# supplies.net
KiCad netlist of a schematic drawn in Altium Designer
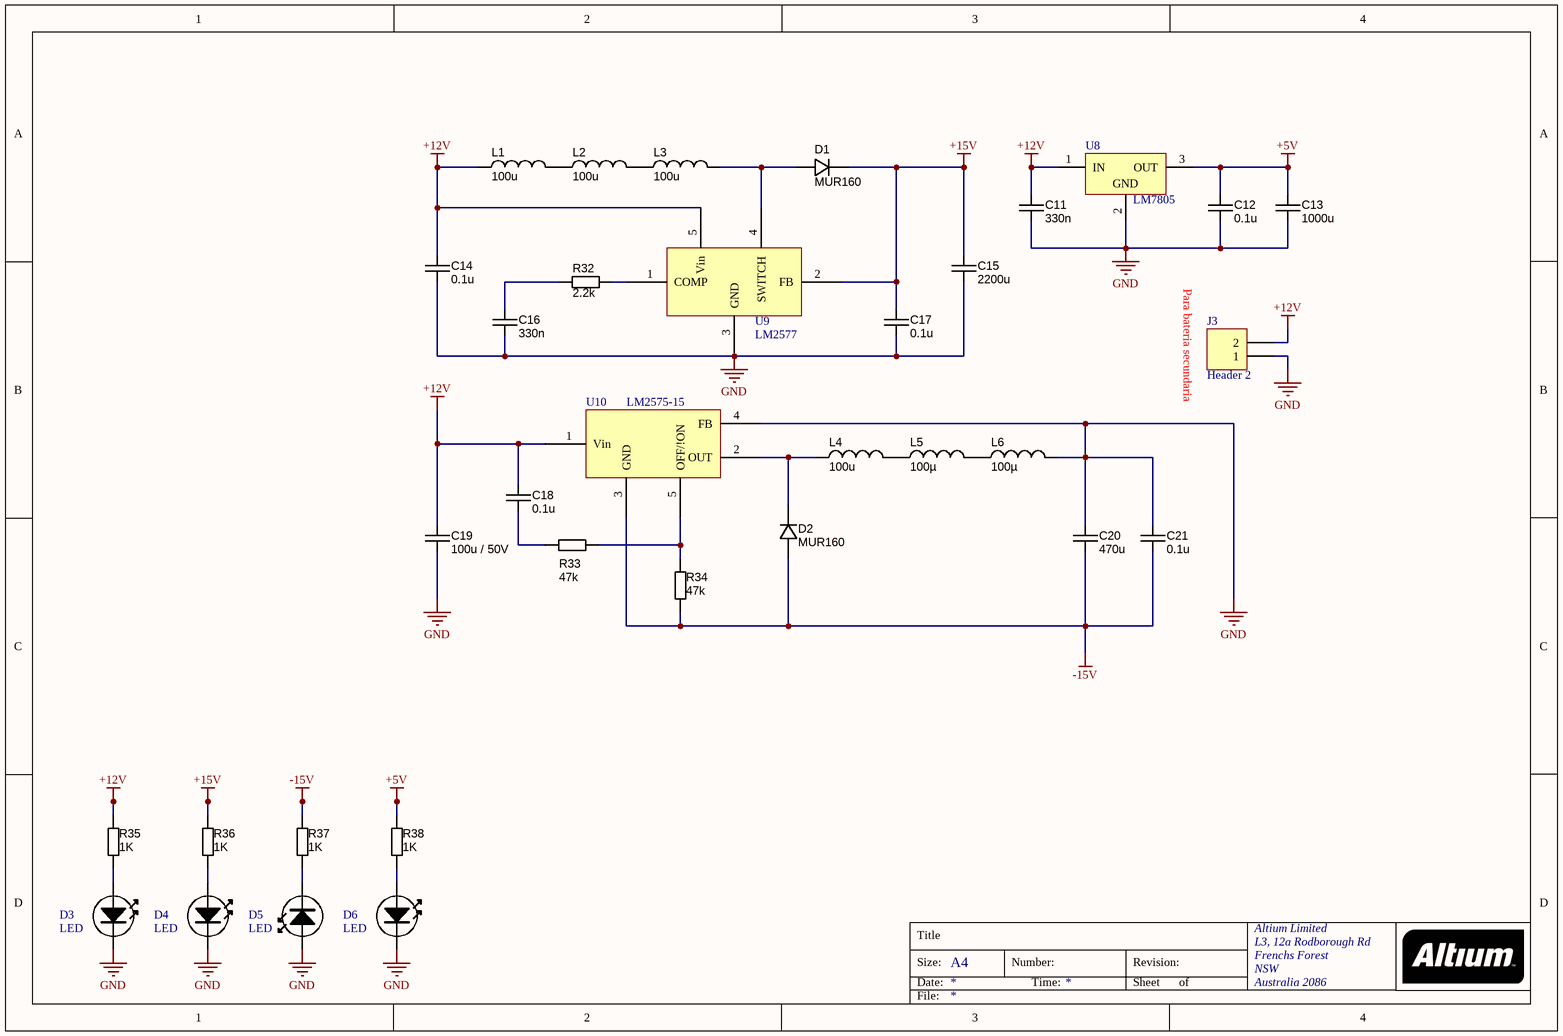
[diagram p0: supplies.SchDoc]

(export (version "E")
  (design (tool "Eeschema 10.0.6"))
  (components
    (comp (ref "C11")
      (value "330n")
      (footprint "cap33n63v")
      (description "Capacitor SMD Cer 330nF 10% 25V X7R 0805")
      (fields (field (name "TOLERANCE") "±10%") (field (name "MANUFACTURER") "Kemet"))
      (libsource (lib "PBL - Capacitors") (part "CAPC_330n_0805"))
    )
    (comp (ref "C12")
      (value "0.1u")
      (footprint "cap100n")
      (description "Capacitor SMD Cer 330nF 10% 25V X7R 0805")
      (fields (field (name "TOLERANCE") "±10%") (field (name "MANUFACTURER") "Kemet"))
      (libsource (lib "PBL - Capacitors") (part "CAPC_330n_0805"))
    )
    (comp (ref "C13")
      (value "1000u")
      (footprint "cap1000u25v")
      (description "Capacitor SMD Cer 330nF 10% 25V X7R 0805")
      (fields (field (name "TOLERANCE") "±10%") (field (name "MANUFACTURER") "Kemet"))
      (libsource (lib "PBL - Capacitors") (part "CAPC_330n_0805"))
    )
    (comp (ref "C14")
      (value "0.1u")
      (footprint "cap100n")
      (description "Capacitor SMD Cer 330nF 10% 25V X7R 0805")
      (fields (field (name "TOLERANCE") "±10%") (field (name "MANUFACTURER") "Kemet"))
      (libsource (lib "PBL - Capacitors") (part "CAPC_330n_0805"))
    )
    (comp (ref "C15")
      (value "2200u")
      (footprint "cap2200u25v")
      (description "Capacitor SMD Cer 330nF 10% 25V X7R 0805")
      (fields (field (name "TOLERANCE") "±10%") (field (name "MANUFACTURER") "Kemet"))
      (libsource (lib "PBL - Capacitors") (part "CAPC_330n_0805"))
    )
    (comp (ref "C16")
      (value "330n")
      (footprint "cap33n63v")
      (description "Capacitor SMD Cer 330nF 10% 25V X7R 0805")
      (fields (field (name "TOLERANCE") "±10%") (field (name "MANUFACTURER") "Kemet"))
      (libsource (lib "PBL - Capacitors") (part "CAPC_330n_0805"))
    )
    (comp (ref "C17")
      (value "0.1u")
      (footprint "cap100n")
      (description "Capacitor SMD Cer 330nF 10% 25V X7R 0805")
      (fields (field (name "TOLERANCE") "±10%") (field (name "MANUFACTURER") "Kemet"))
      (libsource (lib "PBL - Capacitors") (part "CAPC_330n_0805"))
    )
    (comp (ref "C18")
      (value "0.1u")
      (footprint "cap100n")
      (description "Capacitor SMD Cer 330nF 10% 25V X7R 0805")
      (fields (field (name "TOLERANCE") "±10%") (field (name "MANUFACTURER") "Kemet"))
      (libsource (lib "PBL - Capacitors") (part "CAPC_330n_0805"))
    )
    (comp (ref "C19")
      (value "100u / 50V")
      (footprint "cap100u35v")
      (description "Capacitor SMD Cer 330nF 10% 25V X7R 0805")
      (fields (field (name "TOLERANCE") "±10%") (field (name "MANUFACTURER") "Kemet"))
      (libsource (lib "PBL - Capacitors") (part "CAPC_330n_0805"))
    )
    (comp (ref "C20")
      (value "470u")
      (footprint "cap470u50v")
      (description "Capacitor SMD Cer 330nF 10% 25V X7R 0805")
      (fields (field (name "TOLERANCE") "±10%") (field (name "MANUFACTURER") "Kemet"))
      (libsource (lib "PBL - Capacitors") (part "CAPC_330n_0805"))
    )
    (comp (ref "C21")
      (value "0.1u")
      (footprint "cap100n")
      (description "Capacitor SMD Cer 330nF 10% 25V X7R 0805")
      (fields (field (name "TOLERANCE") "±10%") (field (name "MANUFACTURER") "Kemet"))
      (libsource (lib "PBL - Capacitors") (part "CAPC_330n_0805"))
    )
    (comp (ref "D1")
      (value "MUR160")
      (footprint "DO-41")
      (description "Diode 1N4007 1A 1000V THD")
      (libsource (lib "PBL - Diodes") (part "DIODE_1N4007_1000V_1.0A_DO-41"))
    )
    (comp (ref "D2")
      (value "MUR160")
      (footprint "DO-41")
      (description "Diode 1N4007 1A 1000V THD")
      (libsource (lib "PBL - Diodes") (part "DIODE_1N4007_1000V_1.0A_DO-41"))
    )
    (comp (ref "D3")
      (value "LED")
      (footprint "LED-3MM-BLUE")
      (description "LED-BLUE-3MM")
      (libsource (lib "vh_altium_library") (part "LED-BLUE-3MM"))
    )
    (comp (ref "D4")
      (value "LED")
      (footprint "LED-3MM-BLUE")
      (description "LED-BLUE-3MM")
      (libsource (lib "vh_altium_library") (part "LED-BLUE-3MM"))
    )
    (comp (ref "D5")
      (value "LED")
      (footprint "LED-3MM-BLUE")
      (description "LED-BLUE-3MM")
      (libsource (lib "vh_altium_library") (part "LED-BLUE-3MM"))
    )
    (comp (ref "D6")
      (value "LED")
      (footprint "LED-3MM-BLUE")
      (description "LED-BLUE-3MM")
      (libsource (lib "vh_altium_library") (part "LED-BLUE-3MM"))
    )
    (comp (ref "J3")
      (value "Header 2")
      (footprint "HDR1X2")
      (description "Header, 2-Pin")
      (fields (field (name "PUBLISHER") "Altium Limited"))
      (libsource (lib "Miscellaneous Connectors") (part "Header 2"))
    )
    (comp (ref "L1")
      (value "100u")
      (footprint "Inductor")
      (description "Power Inductor 180µH 10% SMD Toroid")
      (fields (field (name "TOLERANCE") "±10%") (field (name "Comment") "INDC_180u_Toroid"))
      (libsource (lib "PBL - Inductors") (part "INDC_180u_Toroid"))
    )
    (comp (ref "L2")
      (value "100u")
      (footprint "Inductor")
      (description "Power Inductor 180µH 10% SMD Toroid")
      (fields (field (name "TOLERANCE") "±10%") (field (name "Comment") "INDC_180u_Toroid"))
      (libsource (lib "PBL - Inductors") (part "INDC_180u_Toroid"))
    )
    (comp (ref "L3")
      (value "100u")
      (footprint "Inductor")
      (description "Power Inductor 180µH 10% SMD Toroid")
      (fields (field (name "TOLERANCE") "±10%") (field (name "Comment") "INDC_180u_Toroid"))
      (libsource (lib "PBL - Inductors") (part "INDC_180u_Toroid"))
    )
    (comp (ref "L4")
      (value "100u")
      (footprint "Inductor")
      (description "Power Inductor 180µH 10% SMD Toroid")
      (fields (field (name "TOLERANCE") "±10%") (field (name "Comment") "INDC_180u_Toroid"))
      (libsource (lib "PBL - Inductors") (part "INDC_180u_Toroid"))
    )
    (comp (ref "L5")
      (value "100µ")
      (footprint "Inductor")
      (description "Power Inductor 180µH 10% SMD Toroid")
      (fields (field (name "TOLERANCE") "±10%") (field (name "Comment") "INDC_180u_Toroid"))
      (libsource (lib "PBL - Inductors") (part "INDC_180u_Toroid"))
    )
    (comp (ref "L6")
      (value "100µ")
      (footprint "Inductor")
      (description "Power Inductor 180µH 10% SMD Toroid")
      (fields (field (name "TOLERANCE") "±10%") (field (name "Comment") "INDC_180u_Toroid"))
      (libsource (lib "PBL - Inductors") (part "INDC_180u_Toroid"))
    )
    (comp (ref "R32")
      (value "2.2k")
      (footprint "RESTH_AXIAL-0.4")
      (description "Resistor THD Axial 1k Ohm 0.25W 5% Carbon Film")
      (fields (field (name "TOLERANCE") "±5%") (field (name "Comment") "Carbon Film"))
      (libsource (lib "") (part "RES_1K_Axial_0.25W_5%_2"))
    )
    (comp (ref "R33")
      (value "47k")
      (footprint "RESTH_AXIAL-0.4")
      (description "Resistor THD Axial 1k Ohm 0.25W 5% Carbon Film")
      (fields (field (name "TOLERANCE") "±5%") (field (name "Comment") "Carbon Film"))
      (libsource (lib "") (part "RES_1K_Axial_0.25W_5%_1"))
    )
    (comp (ref "R34")
      (value "47k")
      (footprint "RESTH_AXIAL-0.4")
      (description "Resistor THD Axial 1k Ohm 0.25W 5% Carbon Film")
      (fields (field (name "TOLERANCE") "±5%") (field (name "Comment") "Carbon Film"))
      (libsource (lib "PBL - Resistors") (part "RES_1K_Axial_0.25W_5%"))
    )
    (comp (ref "R35")
      (value "1K")
      (footprint "RESTH_AXIAL-0.4")
      (description "Resistor THD Axial 1k Ohm 0.25W 5% Carbon Film")
      (fields (field (name "TOLERANCE") "±5%") (field (name "Comment") "Carbon Film"))
      (libsource (lib "PBL - Resistors") (part "RES_1K_Axial_0.25W_5%"))
    )
    (comp (ref "R36")
      (value "1K")
      (footprint "RESTH_AXIAL-0.4")
      (description "Resistor THD Axial 1k Ohm 0.25W 5% Carbon Film")
      (fields (field (name "TOLERANCE") "±5%") (field (name "Comment") "Carbon Film"))
      (libsource (lib "PBL - Resistors") (part "RES_1K_Axial_0.25W_5%"))
    )
    (comp (ref "R37")
      (value "1K")
      (footprint "RESTH_AXIAL-0.4")
      (description "Resistor THD Axial 1k Ohm 0.25W 5% Carbon Film")
      (fields (field (name "TOLERANCE") "±5%") (field (name "Comment") "Carbon Film"))
      (libsource (lib "PBL - Resistors") (part "RES_1K_Axial_0.25W_5%"))
    )
    (comp (ref "R38")
      (value "1K")
      (footprint "RESTH_AXIAL-0.4")
      (description "Resistor THD Axial 1k Ohm 0.25W 5% Carbon Film")
      (fields (field (name "TOLERANCE") "±5%") (field (name "Comment") "Carbon Film"))
      (libsource (lib "PBL - Resistors") (part "RES_1K_Axial_0.25W_5%"))
    )
    (comp (ref "U8")
      (value "LM7805")
      (footprint "T03B")
      (description "3-Terminal Positive Voltage Regulators, 3-pin TO-220")
      (fields
        (field (name "PARTNUMBER") "LM78M05CT")
        (field (name "MANUFACTURER") "National Semiconductor")
        (field (name "PUBLISHER") "Altium Limited")
      )
      (libsource (lib "NSC LDO") (part "LM78M05CT"))
    )
    (comp (ref "U9")
      (value "LM2577")
      (footprint "T05A")
      (description "Boost")
      (libsource (lib "texas instruments") (part "LM2577"))
    )
    (comp (ref "U10")
      (value "LM2575-15")
      (footprint "T05A")
      (description "Buck")
      (libsource (lib "texas instruments") (part "LM2575"))
    )
  )
  (nets
    (net (code "1") (name "+5V") (class "Default")
      (node (ref "C12") (pin "2") (pintype "passive"))
      (node (ref "C13") (pin "2") (pintype "passive"))
      (node (ref "R38") (pin "2") (pinfunction "2_2") (pintype "passive"))
      (node (ref "U8") (pin "3") (pinfunction "OUT_3") (pintype "power_in"))
    )
    (net (code "2") (name "+12V") (class "Default")
      (node (ref "C11") (pin "2") (pintype "passive"))
      (node (ref "C14") (pin "2") (pintype "passive"))
      (node (ref "C18") (pin "2") (pintype "passive"))
      (node (ref "C19") (pin "2") (pintype "passive"))
      (node (ref "J3") (pin "2") (pinfunction "2_2") (pintype "passive"))
      (node (ref "L1") (pin "1") (pinfunction "1_1") (pintype "passive"))
      (node (ref "R35") (pin "2") (pinfunction "2_2") (pintype "passive"))
      (node (ref "U10") (pin "1") (pinfunction "Vin_1") (pintype "passive"))
      (node (ref "U8") (pin "1") (pinfunction "IN_1") (pintype "power_in"))
      (node (ref "U9") (pin "5") (pinfunction "Vin_5") (pintype "passive"))
    )
    (net (code "3") (name "+15V") (class "Default")
      (node (ref "C15") (pin "2") (pintype "passive"))
      (node (ref "C17") (pin "2") (pintype "passive"))
      (node (ref "D1") (pin "K") (pinfunction "K_K") (pintype "passive"))
      (node (ref "R36") (pin "2") (pinfunction "2_2") (pintype "passive"))
      (node (ref "U9") (pin "2") (pinfunction "FB_2") (pintype "passive"))
    )
    (net (code "4") (name "-15V") (class "Default")
      (node (ref "C20") (pin "1") (pintype "passive"))
      (node (ref "C21") (pin "1") (pintype "passive"))
      (node (ref "D2") (pin "A") (pinfunction "A_A") (pintype "passive"))
      (node (ref "R34") (pin "1") (pinfunction "1_1") (pintype "passive"))
      (node (ref "R37") (pin "2") (pinfunction "2_2") (pintype "passive"))
      (node (ref "U10") (pin "3") (pinfunction "GND_3") (pintype "passive"))
    )
    (net (code "5") (name "GND") (class "Default")
      (node (ref "C11") (pin "1") (pintype "passive"))
      (node (ref "C12") (pin "1") (pintype "passive"))
      (node (ref "C13") (pin "1") (pintype "passive"))
      (node (ref "C14") (pin "1") (pintype "passive"))
      (node (ref "C15") (pin "1") (pintype "passive"))
      (node (ref "C16") (pin "1") (pintype "passive"))
      (node (ref "C17") (pin "1") (pintype "passive"))
      (node (ref "C19") (pin "1") (pintype "passive"))
      (node (ref "C20") (pin "2") (pintype "passive"))
      (node (ref "C21") (pin "2") (pintype "passive"))
      (node (ref "D3") (pin "K") (pintype "passive"))
      (node (ref "D4") (pin "K") (pintype "passive"))
      (node (ref "D5") (pin "A") (pintype "passive"))
      (node (ref "D6") (pin "K") (pintype "passive"))
      (node (ref "J3") (pin "1") (pinfunction "1_1") (pintype "passive"))
      (node (ref "L6") (pin "2") (pinfunction "2_2") (pintype "passive"))
      (node (ref "U10") (pin "4") (pinfunction "FB_4") (pintype "passive"))
      (node (ref "U8") (pin "2") (pinfunction "GND_2") (pintype "power_in"))
      (node (ref "U9") (pin "3") (pinfunction "GND_3") (pintype "passive"))
    )
    (net (code "6") (name "Net-(C16-Pad2)") (class "Default")
      (node (ref "C16") (pin "2") (pintype "passive"))
      (node (ref "R32") (pin "2") (pinfunction "2_2") (pintype "passive"))
    )
    (net (code "7") (name "Net-(C18-Pad1)") (class "Default")
      (node (ref "C18") (pin "1") (pintype "passive"))
      (node (ref "R33") (pin "1") (pinfunction "1_1") (pintype "passive"))
    )
    (net (code "8") (name "Net-(D3-PadA)") (class "Default")
      (node (ref "D3") (pin "A") (pintype "passive"))
      (node (ref "R35") (pin "1") (pinfunction "1_1") (pintype "passive"))
    )
    (net (code "9") (name "Net-(D4-PadA)") (class "Default")
      (node (ref "D4") (pin "A") (pintype "passive"))
      (node (ref "R36") (pin "1") (pinfunction "1_1") (pintype "passive"))
    )
    (net (code "10") (name "Net-(D5-PadK)") (class "Default")
      (node (ref "D5") (pin "K") (pintype "passive"))
      (node (ref "R37") (pin "1") (pinfunction "1_1") (pintype "passive"))
    )
    (net (code "11") (name "Net-(D6-PadA)") (class "Default")
      (node (ref "D6") (pin "A") (pintype "passive"))
      (node (ref "R38") (pin "1") (pinfunction "1_1") (pintype "passive"))
    )
    (net (code "12") (name "Net-(L1-Pad2)") (class "Default")
      (node (ref "L1") (pin "2") (pinfunction "2_2") (pintype "passive"))
      (node (ref "L2") (pin "1") (pinfunction "1_1") (pintype "passive"))
    )
    (net (code "13") (name "Net-(L2-Pad2)") (class "Default")
      (node (ref "L2") (pin "2") (pinfunction "2_2") (pintype "passive"))
      (node (ref "L3") (pin "1") (pinfunction "1_1") (pintype "passive"))
    )
    (net (code "14") (name "Net-(L4-Pad2)") (class "Default")
      (node (ref "L4") (pin "2") (pinfunction "2_2") (pintype "passive"))
      (node (ref "L5") (pin "1") (pinfunction "1_1") (pintype "passive"))
    )
    (net (code "15") (name "Net-(L5-Pad2)") (class "Default")
      (node (ref "L5") (pin "2") (pinfunction "2_2") (pintype "passive"))
      (node (ref "L6") (pin "1") (pinfunction "1_1") (pintype "passive"))
    )
    (net (code "16") (name "Net-(U9-COMP)") (class "Default")
      (node (ref "R32") (pin "1") (pinfunction "1_1") (pintype "passive"))
      (node (ref "U9") (pin "1") (pinfunction "COMP_1") (pintype "passive"))
    )
    (net (code "17") (name "Net-(U9-SWITCH)") (class "Default")
      (node (ref "D1") (pin "A") (pinfunction "A_A") (pintype "passive"))
      (node (ref "L3") (pin "2") (pinfunction "2_2") (pintype "passive"))
      (node (ref "U9") (pin "4") (pinfunction "SWITCH_4") (pintype "passive"))
    )
    (net (code "18") (name "Net-(U10-OFF{slash}!ON)") (class "Default")
      (node (ref "R33") (pin "2") (pinfunction "2_2") (pintype "passive"))
      (node (ref "R34") (pin "2") (pinfunction "2_2") (pintype "passive"))
      (node (ref "U10") (pin "5") (pinfunction "OFF/!ON_5") (pintype "passive"))
    )
    (net (code "19") (name "Net-(U10-OUT)") (class "Default")
      (node (ref "D2") (pin "K") (pinfunction "K_K") (pintype "passive"))
      (node (ref "L4") (pin "1") (pinfunction "1_1") (pintype "passive"))
      (node (ref "U10") (pin "2") (pinfunction "OUT_2") (pintype "passive"))
    )
  )
)
